# Panasonic-Aquarea-ESP32_SCH_V3_8.net
KiCad netlist of a schematic drawn in EasyEDA
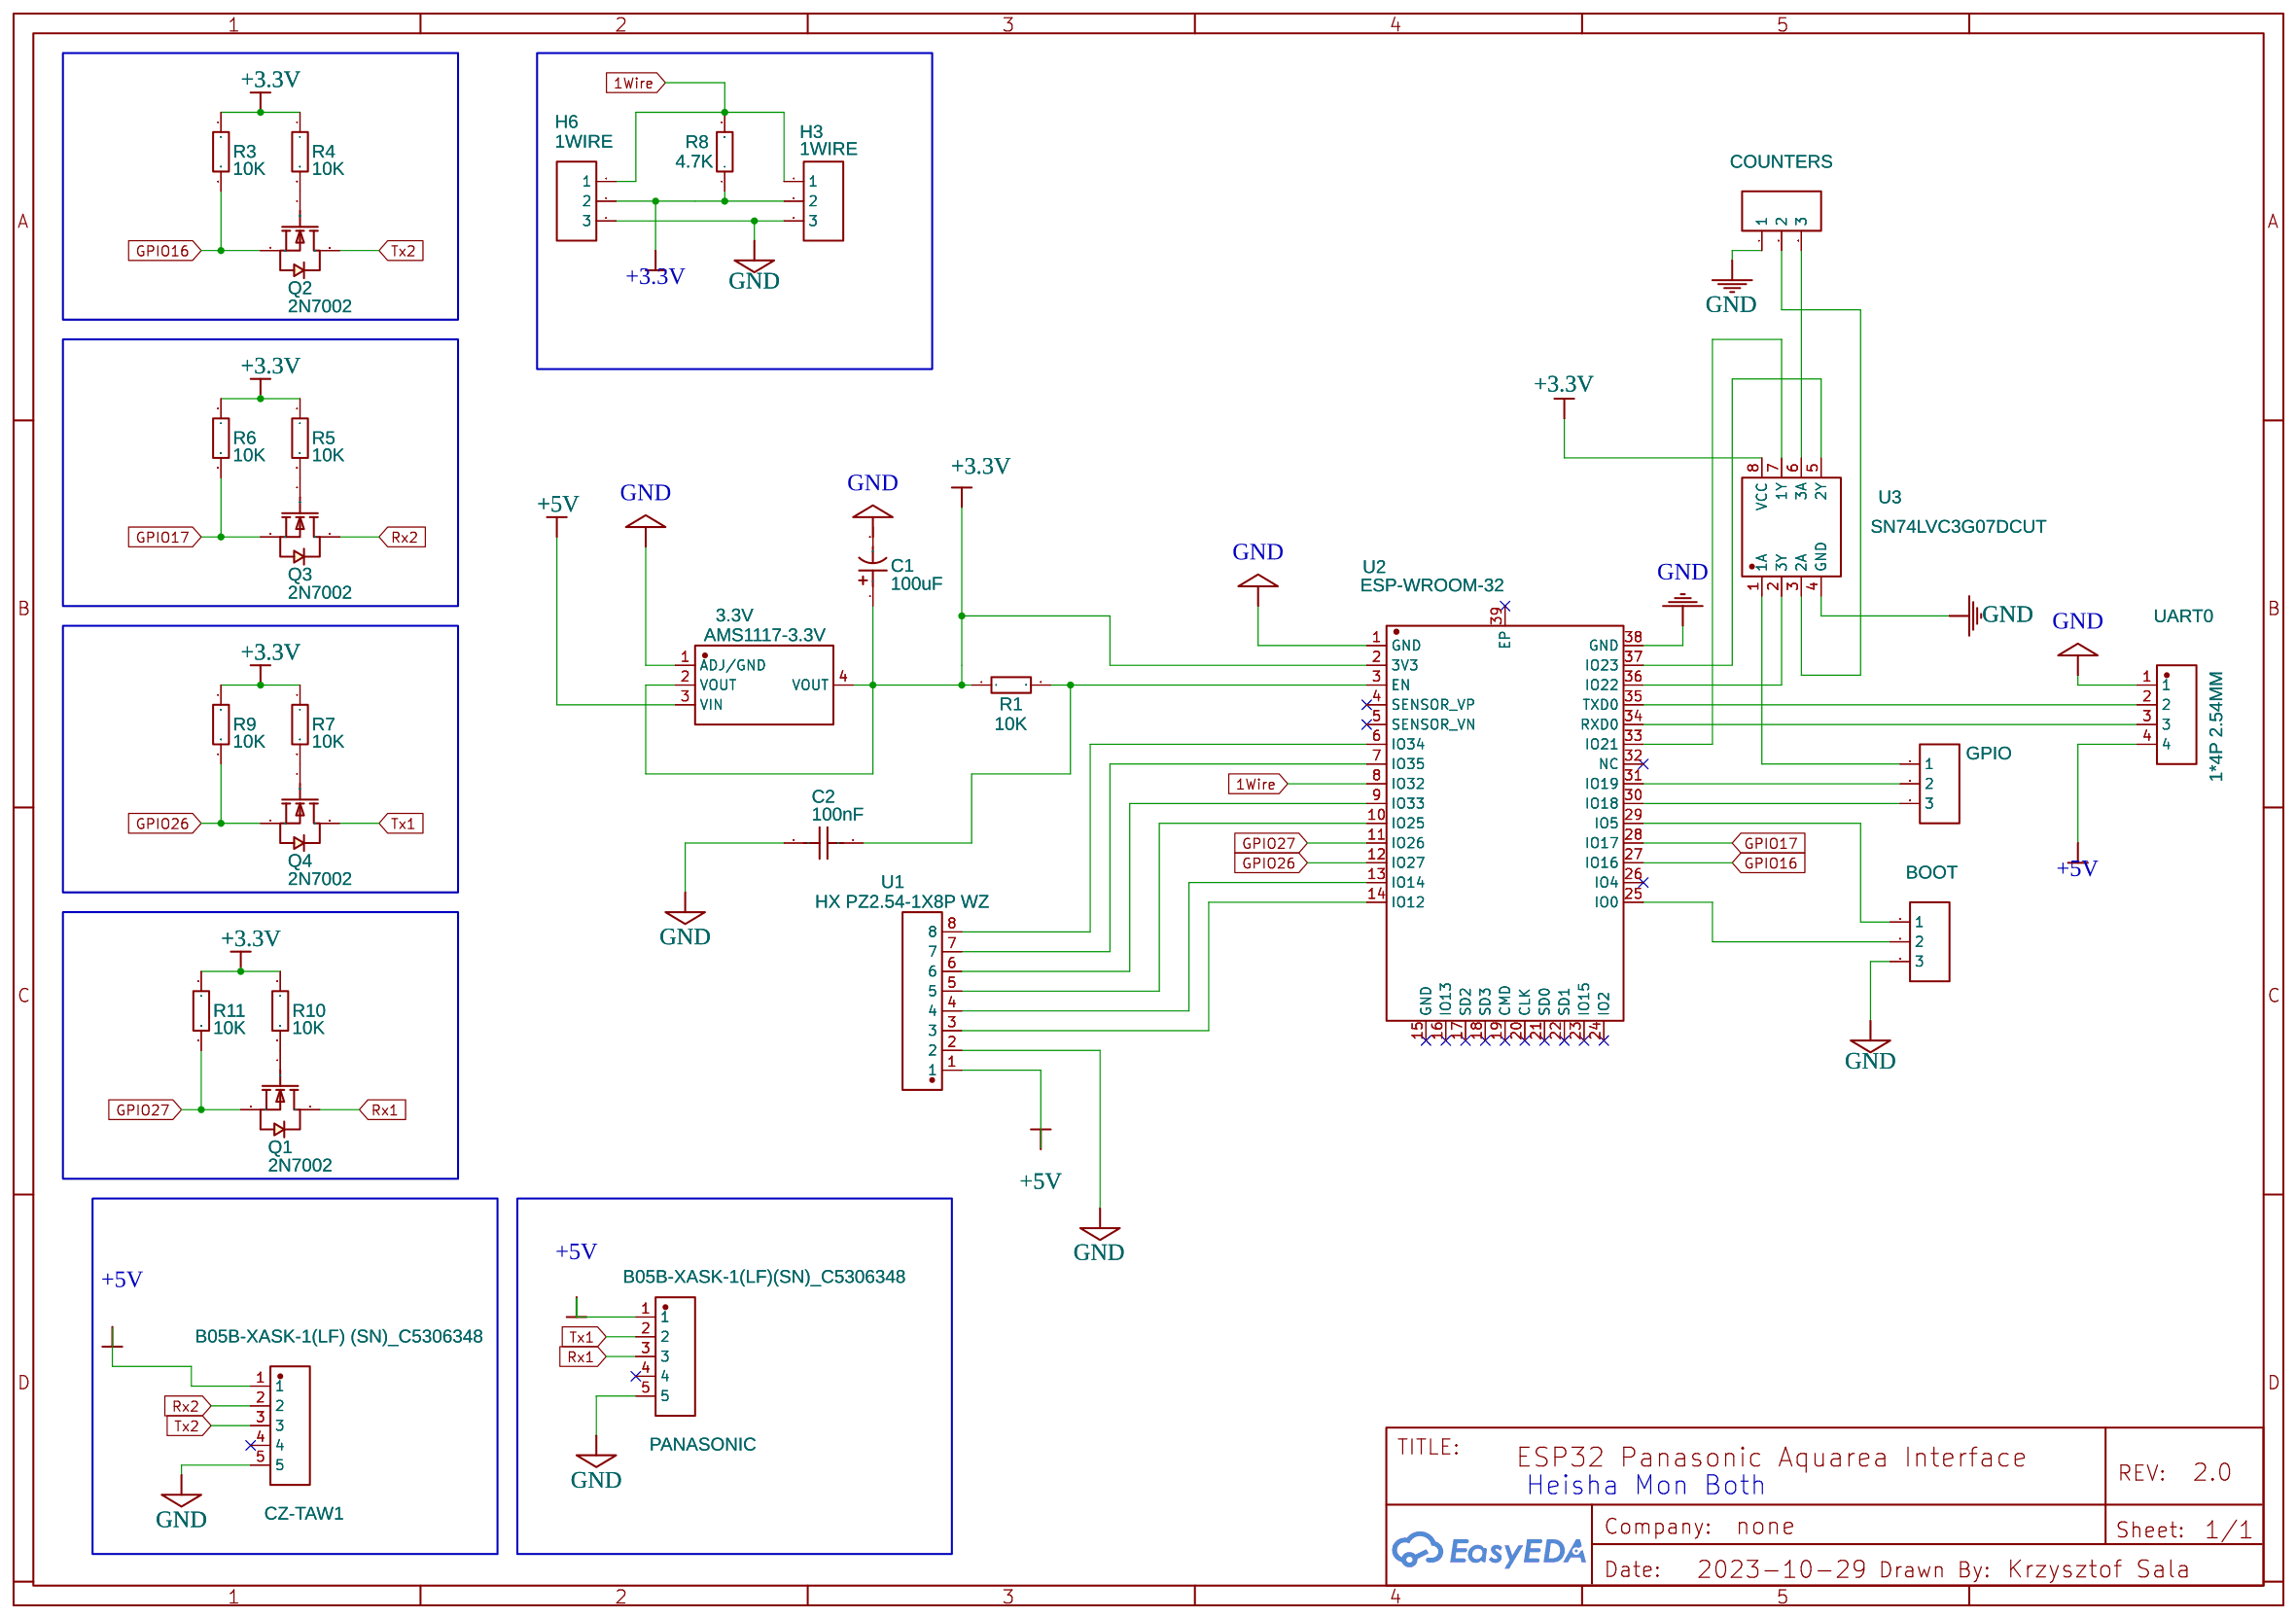
[diagram p0: schematic sheet]

(export (version "E")
  (design (tool "Eeschema 10.0.6"))
  (components
    (comp (ref "3.3V")
      (value "AMS1117-3.3V")
      (fields (field (name "Manufacturer") "WPMtek(维攀微)"))
      (libsource (lib "") (part "AMS1117-3.3V"))
    )
    (comp (ref "BOOT")
      (value "S0 coounters")
      (fields (field (name "Manufacturer Part") "Header2.54mm 1*3P") (field (name "Manufacturer") "BOOMELE"))
      (libsource (lib "") (part "Unknown_965_470"))
    )
    (comp (ref "C1")
      (value "100uF")
      (fields (field (name "Manufacturer Part") "HS1C107M0507PC") (field (name "Manufacturer") "HONOR(荣誉)"))
      (libsource (lib "") (part "HS1C107M0507PC"))
    )
    (comp (ref "C2")
      (value "100nF")
      (fields
        (field (name "Manufacturer Part") "GRM31C5C1E104JA01L")
        (field (name "Manufacturer") "muRata(村田)")
      )
      (libsource (lib "") (part "GRM31C5C1E104JA01L_C426117"))
    )
    (comp (ref "COUNTERS")
      (value "S0 coounters")
      (fields (field (name "Manufacturer Part") "Header2.54mm 1*3P") (field (name "Manufacturer") "BOOMELE"))
      (libsource (lib "") (part "Unknown_895_105"))
    )
    (comp (ref "CZ-TAW1")
      (value "B05B-XASK-1(LF) (SN)_C5306348")
      (fields (field (name "Manufacturer Part") "B05B-XASK-1(LF)(SN)") (field (name "Manufacturer") "JST"))
      (libsource (lib "") (part "B05B-XASK-1(LF)(SN)_C5306348"))
    )
    (comp (ref "GPIO")
      (value "S0 coounters")
      (fields (field (name "Manufacturer Part") "Header2.54mm 1*3P") (field (name "Manufacturer") "BOOMELE"))
      (libsource (lib "") (part "Unknown_970_390"))
    )
    (comp (ref "H3")
      (value "1WIRE")
      (fields (field (name "Manufacturer Part") "Header2.54mm 1*3P") (field (name "Manufacturer") "BOOMELE"))
      (libsource (lib "") (part "Unknown_405_95"))
    )
    (comp (ref "H6")
      (value "1WIRE")
      (fields (field (name "Manufacturer Part") "Header2.54mm 1*3P") (field (name "Manufacturer") "BOOMELE"))
      (libsource (lib "") (part "Unknown_290_95"))
    )
    (comp (ref "PANASONIC")
      (value "B05B-XASK-1(LF)(SN)_C5306348")
      (fields (field (name "Manufacturer Part") "B05B-XASK-1(LF)(SN)") (field (name "Manufacturer") "JST"))
      (libsource (lib "") (part "B05B-XASK-1(LF)(SN)_C5306348_1"))
    )
    (comp (ref "Q1")
      (value "2N7002")
      (fields (field (name "Manufacturer") "CJ"))
      (libsource (lib "") (part "Unknown_135_545"))
    )
    (comp (ref "Q2")
      (value "2N7002")
      (fields (field (name "Manufacturer") "CJ"))
      (libsource (lib "") (part "Unknown_145_110"))
    )
    (comp (ref "Q3")
      (value "2N7002")
      (fields (field (name "Manufacturer") "CJ"))
      (libsource (lib "") (part "Unknown_145_255"))
    )
    (comp (ref "Q4")
      (value "2N7002")
      (fields (field (name "Manufacturer") "CJ"))
      (libsource (lib "") (part "Unknown_145_400"))
    )
    (comp (ref "R1")
      (value "10K")
      (fields (field (name "Manufacturer Part") "0603WAF1002T5E") (field (name "Manufacturer") "UniOhm"))
      (libsource (lib "") (part "0603WAF1002T5E_1"))
    )
    (comp (ref "R3")
      (value "10K")
      (fields (field (name "Manufacturer Part") "0603WAF1002T5E") (field (name "Manufacturer") "UniOhm"))
      (libsource (lib "") (part "0603WAF1002T5E"))
    )
    (comp (ref "R4")
      (value "10K")
      (fields (field (name "Manufacturer Part") "0603WAF1002T5E") (field (name "Manufacturer") "UniOhm"))
      (libsource (lib "") (part "0603WAF1002T5E"))
    )
    (comp (ref "R5")
      (value "10K")
      (fields (field (name "Manufacturer Part") "0603WAF1002T5E") (field (name "Manufacturer") "UniOhm"))
      (libsource (lib "") (part "0603WAF1002T5E"))
    )
    (comp (ref "R6")
      (value "10K")
      (fields (field (name "Manufacturer Part") "0603WAF1002T5E") (field (name "Manufacturer") "UniOhm"))
      (libsource (lib "") (part "0603WAF1002T5E"))
    )
    (comp (ref "R7")
      (value "10K")
      (fields (field (name "Manufacturer Part") "0603WAF1002T5E") (field (name "Manufacturer") "UniOhm"))
      (libsource (lib "") (part "0603WAF1002T5E"))
    )
    (comp (ref "R8")
      (value "4.7K")
      (fields (field (name "Manufacturer Part") "0603WAF4701T5E") (field (name "Manufacturer") "UniOhm"))
      (libsource (lib "") (part "0603WAF4701T5E"))
    )
    (comp (ref "R9")
      (value "10K")
      (fields (field (name "Manufacturer Part") "0603WAF1002T5E") (field (name "Manufacturer") "UniOhm"))
      (libsource (lib "") (part "0603WAF1002T5E"))
    )
    (comp (ref "R10")
      (value "10K")
      (fields (field (name "Manufacturer Part") "0603WAF1002T5E") (field (name "Manufacturer") "UniOhm"))
      (libsource (lib "") (part "0603WAF1002T5E"))
    )
    (comp (ref "R11")
      (value "10K")
      (fields (field (name "Manufacturer Part") "0603WAF1002T5E") (field (name "Manufacturer") "UniOhm"))
      (libsource (lib "") (part "0603WAF1002T5E"))
    )
    (comp (ref "U1")
      (value "HX PZ2.54-1X8P WZ")
      (fields
        (field (name "Manufacturer Part") "HX PZ2.54-1x8P WZ")
        (field (name "Manufacturer") "hanxia(韩下)")
      )
      (libsource (lib "") (part "HX PZ2.54-1X8P WZ"))
    )
    (comp (ref "U2")
      (value "ESP-WROOM-32")
      (fields
        (field (name "Manufacturer Part") "ESP32-WROOM-32")
        (field (name "Manufacturer") "ESPRESSIF(乐鑫)")
      )
      (libsource (lib "") (part "ESP-WROOM-32"))
    )
    (comp (ref "U3")
      (value "SN74LVC3G07DCUT")
      (fields (field (name "Manufacturer") "TI(德州仪器)"))
      (libsource (lib "") (part "SN74LVC3G07DCUT"))
    )
    (comp (ref "UART0")
      (value "1*4P 2.54MM")
      (fields (field (name "Manufacturer Part") "单排直插排针 1*4P 2.54mm"))
      (libsource (lib "") (part "1*4P 2.54MM"))
    )
  )
  (nets
    (net (code "1") (name "+3.3V") (class "Default")
      (node (ref "3.3V") (pin "2") (pinfunction "VOUT_2") (pintype "unspecified"))
      (node (ref "3.3V") (pin "4") (pinfunction "VOUT_4") (pintype "unspecified"))
      (node (ref "C1") (pin "1") (pinfunction "1_1") (pintype "input"))
      (node (ref "H3") (pin "2") (pinfunction "2_2") (pintype "input"))
      (node (ref "H6") (pin "2") (pinfunction "2_2") (pintype "input"))
      (node (ref "R1") (pin "1") (pinfunction "1_1") (pintype "input"))
      (node (ref "R10") (pin "1") (pinfunction "1_1") (pintype "input"))
      (node (ref "R11") (pin "1") (pinfunction "1_1") (pintype "input"))
      (node (ref "R3") (pin "1") (pinfunction "1_1") (pintype "input"))
      (node (ref "R4") (pin "1") (pinfunction "1_1") (pintype "input"))
      (node (ref "R5") (pin "1") (pinfunction "1_1") (pintype "input"))
      (node (ref "R6") (pin "1") (pinfunction "1_1") (pintype "input"))
      (node (ref "R7") (pin "1") (pinfunction "1_1") (pintype "input"))
      (node (ref "R8") (pin "1") (pinfunction "1_1") (pintype "input"))
      (node (ref "R9") (pin "1") (pinfunction "1_1") (pintype "input"))
      (node (ref "U2") (pin "2") (pinfunction "3V3_2") (pintype "unspecified"))
      (node (ref "U3") (pin "8") (pinfunction "VCC_8") (pintype "unspecified"))
    )
    (net (code "2") (name "+5V") (class "Default")
      (node (ref "3.3V") (pin "3") (pinfunction "VIN_3") (pintype "unspecified"))
      (node (ref "CZ-TAW1") (pin "1") (pinfunction "1_1") (pintype "unspecified"))
      (node (ref "PANASONIC") (pin "1") (pinfunction "1_1") (pintype "unspecified"))
      (node (ref "U1") (pin "1") (pinfunction "1_1") (pintype "unspecified"))
      (node (ref "UART0") (pin "4") (pinfunction "4_4") (pintype "unspecified"))
    )
    (net (code "3") (name "1Wire") (class "Default")
      (node (ref "H3") (pin "1") (pinfunction "1_1") (pintype "input"))
      (node (ref "H6") (pin "1") (pinfunction "1_1") (pintype "input"))
      (node (ref "R8") (pin "2") (pinfunction "2_2") (pintype "input"))
      (node (ref "U2") (pin "8") (pinfunction "IO32_8") (pintype "unspecified"))
    )
    (net (code "4") (name "GND") (class "Default")
      (node (ref "3.3V") (pin "1") (pinfunction "ADJ/GND_1") (pintype "unspecified"))
      (node (ref "BOOT") (pin "3") (pinfunction "3_3") (pintype "input"))
      (node (ref "C1") (pin "2") (pinfunction "2_2") (pintype "input"))
      (node (ref "C2") (pin "2") (pinfunction "2_2") (pintype "unspecified"))
      (node (ref "COUNTERS") (pin "1") (pinfunction "1_1") (pintype "input"))
      (node (ref "CZ-TAW1") (pin "5") (pinfunction "5_5") (pintype "unspecified"))
      (node (ref "H3") (pin "3") (pinfunction "3_3") (pintype "input"))
      (node (ref "H6") (pin "3") (pinfunction "3_3") (pintype "input"))
      (node (ref "PANASONIC") (pin "5") (pinfunction "5_5") (pintype "unspecified"))
      (node (ref "U1") (pin "2") (pinfunction "2_2") (pintype "unspecified"))
      (node (ref "U2") (pin "1") (pinfunction "GND_1") (pintype "unspecified"))
      (node (ref "U2") (pin "38") (pinfunction "GND_38") (pintype "unspecified"))
      (node (ref "U3") (pin "4") (pinfunction "GND_4") (pintype "unspecified"))
      (node (ref "UART0") (pin "1") (pinfunction "1_1") (pintype "unspecified"))
    )
    (net (code "5") (name "GPIO16") (class "Default")
      (node (ref "Q2") (pin "2") (pinfunction "S_2") (pintype "unspecified"))
      (node (ref "R3") (pin "2") (pinfunction "2_2") (pintype "input"))
      (node (ref "U2") (pin "27") (pinfunction "IO16_27") (pintype "unspecified"))
    )
    (net (code "6") (name "GPIO17") (class "Default")
      (node (ref "Q3") (pin "2") (pinfunction "S_2") (pintype "unspecified"))
      (node (ref "R6") (pin "2") (pinfunction "2_2") (pintype "input"))
      (node (ref "U2") (pin "28") (pinfunction "IO17_28") (pintype "unspecified"))
    )
    (net (code "7") (name "GPIO26") (class "Default")
      (node (ref "Q4") (pin "2") (pinfunction "S_2") (pintype "unspecified"))
      (node (ref "R9") (pin "2") (pinfunction "2_2") (pintype "input"))
      (node (ref "U2") (pin "12") (pinfunction "IO27_12") (pintype "unspecified"))
    )
    (net (code "8") (name "GPIO27") (class "Default")
      (node (ref "Q1") (pin "2") (pinfunction "S_2") (pintype "unspecified"))
      (node (ref "R11") (pin "2") (pinfunction "2_2") (pintype "input"))
      (node (ref "U2") (pin "11") (pinfunction "IO26_11") (pintype "unspecified"))
    )
    (net (code "9") (name "Net-(Q1-G)") (class "Default")
      (node (ref "Q1") (pin "1") (pinfunction "G_1") (pintype "unspecified"))
      (node (ref "R10") (pin "2") (pinfunction "2_2") (pintype "input"))
    )
    (net (code "10") (name "Net-(Q2-G)") (class "Default")
      (node (ref "Q2") (pin "1") (pinfunction "G_1") (pintype "unspecified"))
      (node (ref "R4") (pin "2") (pinfunction "2_2") (pintype "input"))
    )
    (net (code "11") (name "Net-(Q3-G)") (class "Default")
      (node (ref "Q3") (pin "1") (pinfunction "G_1") (pintype "unspecified"))
      (node (ref "R5") (pin "2") (pinfunction "2_2") (pintype "input"))
    )
    (net (code "12") (name "Net-(Q4-G)") (class "Default")
      (node (ref "Q4") (pin "1") (pinfunction "G_1") (pintype "unspecified"))
      (node (ref "R7") (pin "2") (pinfunction "2_2") (pintype "input"))
    )
    (net (code "13") (name "Net-(U2-EN)") (class "Default")
      (node (ref "C2") (pin "1") (pinfunction "1_1") (pintype "unspecified"))
      (node (ref "R1") (pin "2") (pinfunction "2_2") (pintype "input"))
      (node (ref "U2") (pin "3") (pinfunction "EN_3") (pintype "unspecified"))
    )
    (net (code "14") (name "Net-(U2-IO0)") (class "Default")
      (node (ref "BOOT") (pin "2") (pinfunction "2_2") (pintype "input"))
      (node (ref "U2") (pin "25") (pinfunction "IO0_25") (pintype "unspecified"))
    )
    (net (code "15") (name "Net-(U2-IO5)") (class "Default")
      (node (ref "BOOT") (pin "1") (pinfunction "1_1") (pintype "input"))
      (node (ref "U2") (pin "29") (pinfunction "IO5_29") (pintype "unspecified"))
    )
    (net (code "16") (name "Net-(U2-IO12)") (class "Default")
      (node (ref "U1") (pin "3") (pinfunction "3_3") (pintype "unspecified"))
      (node (ref "U2") (pin "14") (pinfunction "IO12_14") (pintype "unspecified"))
    )
    (net (code "17") (name "Net-(U2-IO14)") (class "Default")
      (node (ref "U1") (pin "4") (pinfunction "4_4") (pintype "unspecified"))
      (node (ref "U2") (pin "13") (pinfunction "IO14_13") (pintype "unspecified"))
    )
    (net (code "18") (name "Net-(U2-IO18)") (class "Default")
      (node (ref "GPIO") (pin "3") (pinfunction "3_3") (pintype "input"))
      (node (ref "U2") (pin "30") (pinfunction "IO18_30") (pintype "unspecified"))
    )
    (net (code "19") (name "Net-(U2-IO19)") (class "Default")
      (node (ref "GPIO") (pin "2") (pinfunction "2_2") (pintype "input"))
      (node (ref "U2") (pin "31") (pinfunction "IO19_31") (pintype "unspecified"))
    )
    (net (code "20") (name "Net-(U2-IO21)") (class "Default")
      (node (ref "U2") (pin "33") (pinfunction "IO21_33") (pintype "unspecified"))
      (node (ref "U3") (pin "7") (pinfunction "1Y_7") (pintype "unspecified"))
    )
    (net (code "21") (name "Net-(U2-IO22)") (class "Default")
      (node (ref "U2") (pin "36") (pinfunction "IO22_36") (pintype "unspecified"))
      (node (ref "U3") (pin "2") (pinfunction "3Y_2") (pintype "unspecified"))
    )
    (net (code "22") (name "Net-(U2-IO23)") (class "Default")
      (node (ref "U2") (pin "37") (pinfunction "IO23_37") (pintype "unspecified"))
      (node (ref "U3") (pin "5") (pinfunction "2Y_5") (pintype "unspecified"))
    )
    (net (code "23") (name "Net-(U2-IO25)") (class "Default")
      (node (ref "U1") (pin "5") (pinfunction "5_5") (pintype "unspecified"))
      (node (ref "U2") (pin "10") (pinfunction "IO25_10") (pintype "unspecified"))
    )
    (net (code "24") (name "Net-(U2-IO33)") (class "Default")
      (node (ref "U1") (pin "6") (pinfunction "6_6") (pintype "unspecified"))
      (node (ref "U2") (pin "9") (pinfunction "IO33_9") (pintype "unspecified"))
    )
    (net (code "25") (name "Net-(U2-IO34)") (class "Default")
      (node (ref "U1") (pin "8") (pinfunction "8_8") (pintype "unspecified"))
      (node (ref "U2") (pin "6") (pinfunction "IO34_6") (pintype "unspecified"))
    )
    (net (code "26") (name "Net-(U2-IO35)") (class "Default")
      (node (ref "U1") (pin "7") (pinfunction "7_7") (pintype "unspecified"))
      (node (ref "U2") (pin "7") (pinfunction "IO35_7") (pintype "unspecified"))
    )
    (net (code "27") (name "Net-(U2-RXD0)") (class "Default")
      (node (ref "U2") (pin "34") (pinfunction "RXD0_34") (pintype "unspecified"))
      (node (ref "UART0") (pin "3") (pinfunction "3_3") (pintype "unspecified"))
    )
    (net (code "28") (name "Net-(U2-TXD0)") (class "Default")
      (node (ref "U2") (pin "35") (pinfunction "TXD0_35") (pintype "unspecified"))
      (node (ref "UART0") (pin "2") (pinfunction "2_2") (pintype "unspecified"))
    )
    (net (code "29") (name "Net-(U3-1A)") (class "Default")
      (node (ref "GPIO") (pin "1") (pinfunction "1_1") (pintype "input"))
      (node (ref "U3") (pin "1") (pinfunction "1A_1") (pintype "unspecified"))
    )
    (net (code "30") (name "Net-(U3-2A)") (class "Default")
      (node (ref "COUNTERS") (pin "2") (pinfunction "2_2") (pintype "input"))
      (node (ref "U3") (pin "3") (pinfunction "2A_3") (pintype "unspecified"))
    )
    (net (code "31") (name "Net-(U3-3A)") (class "Default")
      (node (ref "COUNTERS") (pin "3") (pinfunction "3_3") (pintype "input"))
      (node (ref "U3") (pin "6") (pinfunction "3A_6") (pintype "unspecified"))
    )
    (net (code "32") (name "Rx1") (class "Default")
      (node (ref "PANASONIC") (pin "3") (pinfunction "3_3") (pintype "unspecified"))
      (node (ref "Q1") (pin "3") (pinfunction "D_3") (pintype "unspecified"))
    )
    (net (code "33") (name "Rx2") (class "Default")
      (node (ref "CZ-TAW1") (pin "2") (pinfunction "2_2") (pintype "unspecified"))
      (node (ref "Q3") (pin "3") (pinfunction "D_3") (pintype "unspecified"))
    )
    (net (code "34") (name "Tx1") (class "Default")
      (node (ref "PANASONIC") (pin "2") (pinfunction "2_2") (pintype "unspecified"))
      (node (ref "Q4") (pin "3") (pinfunction "D_3") (pintype "unspecified"))
    )
    (net (code "35") (name "Tx2") (class "Default")
      (node (ref "CZ-TAW1") (pin "3") (pinfunction "3_3") (pintype "unspecified"))
      (node (ref "Q2") (pin "3") (pinfunction "D_3") (pintype "unspecified"))
    )
    (net (code "36") (name "unconnected-(CZ-TAW1-Pad4)") (class "Default")
      (node (ref "CZ-TAW1") (pin "4") (pinfunction "4_4") (pintype "unspecified+no_connect"))
    )
    (net (code "37") (name "unconnected-(PANASONIC-Pad4)") (class "Default")
      (node (ref "PANASONIC") (pin "4") (pinfunction "4_4") (pintype "unspecified+no_connect"))
    )
    (net (code "38") (name "unconnected-(U2-CLK-Pad20)") (class "Default")
      (node (ref "U2") (pin "20") (pinfunction "CLK_20") (pintype "unspecified+no_connect"))
    )
    (net (code "39") (name "unconnected-(U2-CMD-Pad19)") (class "Default")
      (node (ref "U2") (pin "19") (pinfunction "CMD_19") (pintype "unspecified+no_connect"))
    )
    (net (code "40") (name "unconnected-(U2-EP-Pad39)") (class "Default")
      (node (ref "U2") (pin "39") (pinfunction "EP_39") (pintype "unspecified+no_connect"))
    )
    (net (code "41") (name "unconnected-(U2-GND-Pad15)") (class "Default")
      (node (ref "U2") (pin "15") (pinfunction "GND_15") (pintype "unspecified+no_connect"))
    )
    (net (code "42") (name "unconnected-(U2-IO2-Pad24)") (class "Default")
      (node (ref "U2") (pin "24") (pinfunction "IO2_24") (pintype "unspecified+no_connect"))
    )
    (net (code "43") (name "unconnected-(U2-IO4-Pad26)") (class "Default")
      (node (ref "U2") (pin "26") (pinfunction "IO4_26") (pintype "unspecified+no_connect"))
    )
    (net (code "44") (name "unconnected-(U2-IO13-Pad16)") (class "Default")
      (node (ref "U2") (pin "16") (pinfunction "IO13_16") (pintype "unspecified+no_connect"))
    )
    (net (code "45") (name "unconnected-(U2-IO15-Pad23)") (class "Default")
      (node (ref "U2") (pin "23") (pinfunction "IO15_23") (pintype "unspecified+no_connect"))
    )
    (net (code "46") (name "unconnected-(U2-NC-Pad32)") (class "Default")
      (node (ref "U2") (pin "32") (pinfunction "NC_32") (pintype "unspecified+no_connect"))
    )
    (net (code "47") (name "unconnected-(U2-SD0-Pad21)") (class "Default")
      (node (ref "U2") (pin "21") (pinfunction "SD0_21") (pintype "unspecified+no_connect"))
    )
    (net (code "48") (name "unconnected-(U2-SD1-Pad22)") (class "Default")
      (node (ref "U2") (pin "22") (pinfunction "SD1_22") (pintype "unspecified+no_connect"))
    )
    (net (code "49") (name "unconnected-(U2-SD2-Pad17)") (class "Default")
      (node (ref "U2") (pin "17") (pinfunction "SD2_17") (pintype "unspecified+no_connect"))
    )
    (net (code "50") (name "unconnected-(U2-SD3-Pad18)") (class "Default")
      (node (ref "U2") (pin "18") (pinfunction "SD3_18") (pintype "unspecified+no_connect"))
    )
    (net (code "51") (name "unconnected-(U2-SENSOR_VN-Pad5)") (class "Default")
      (node (ref "U2") (pin "5") (pinfunction "SENSOR_VN_5") (pintype "unspecified+no_connect"))
    )
    (net (code "52") (name "unconnected-(U2-SENSOR_VP-Pad4)") (class "Default")
      (node (ref "U2") (pin "4") (pinfunction "SENSOR_VP_4") (pintype "unspecified+no_connect"))
    )
  )
)
